# Pinduino-Nano-WPC-TPL521-v0_3c.net
KiCad netlist of a schematic drawn in EAGLE
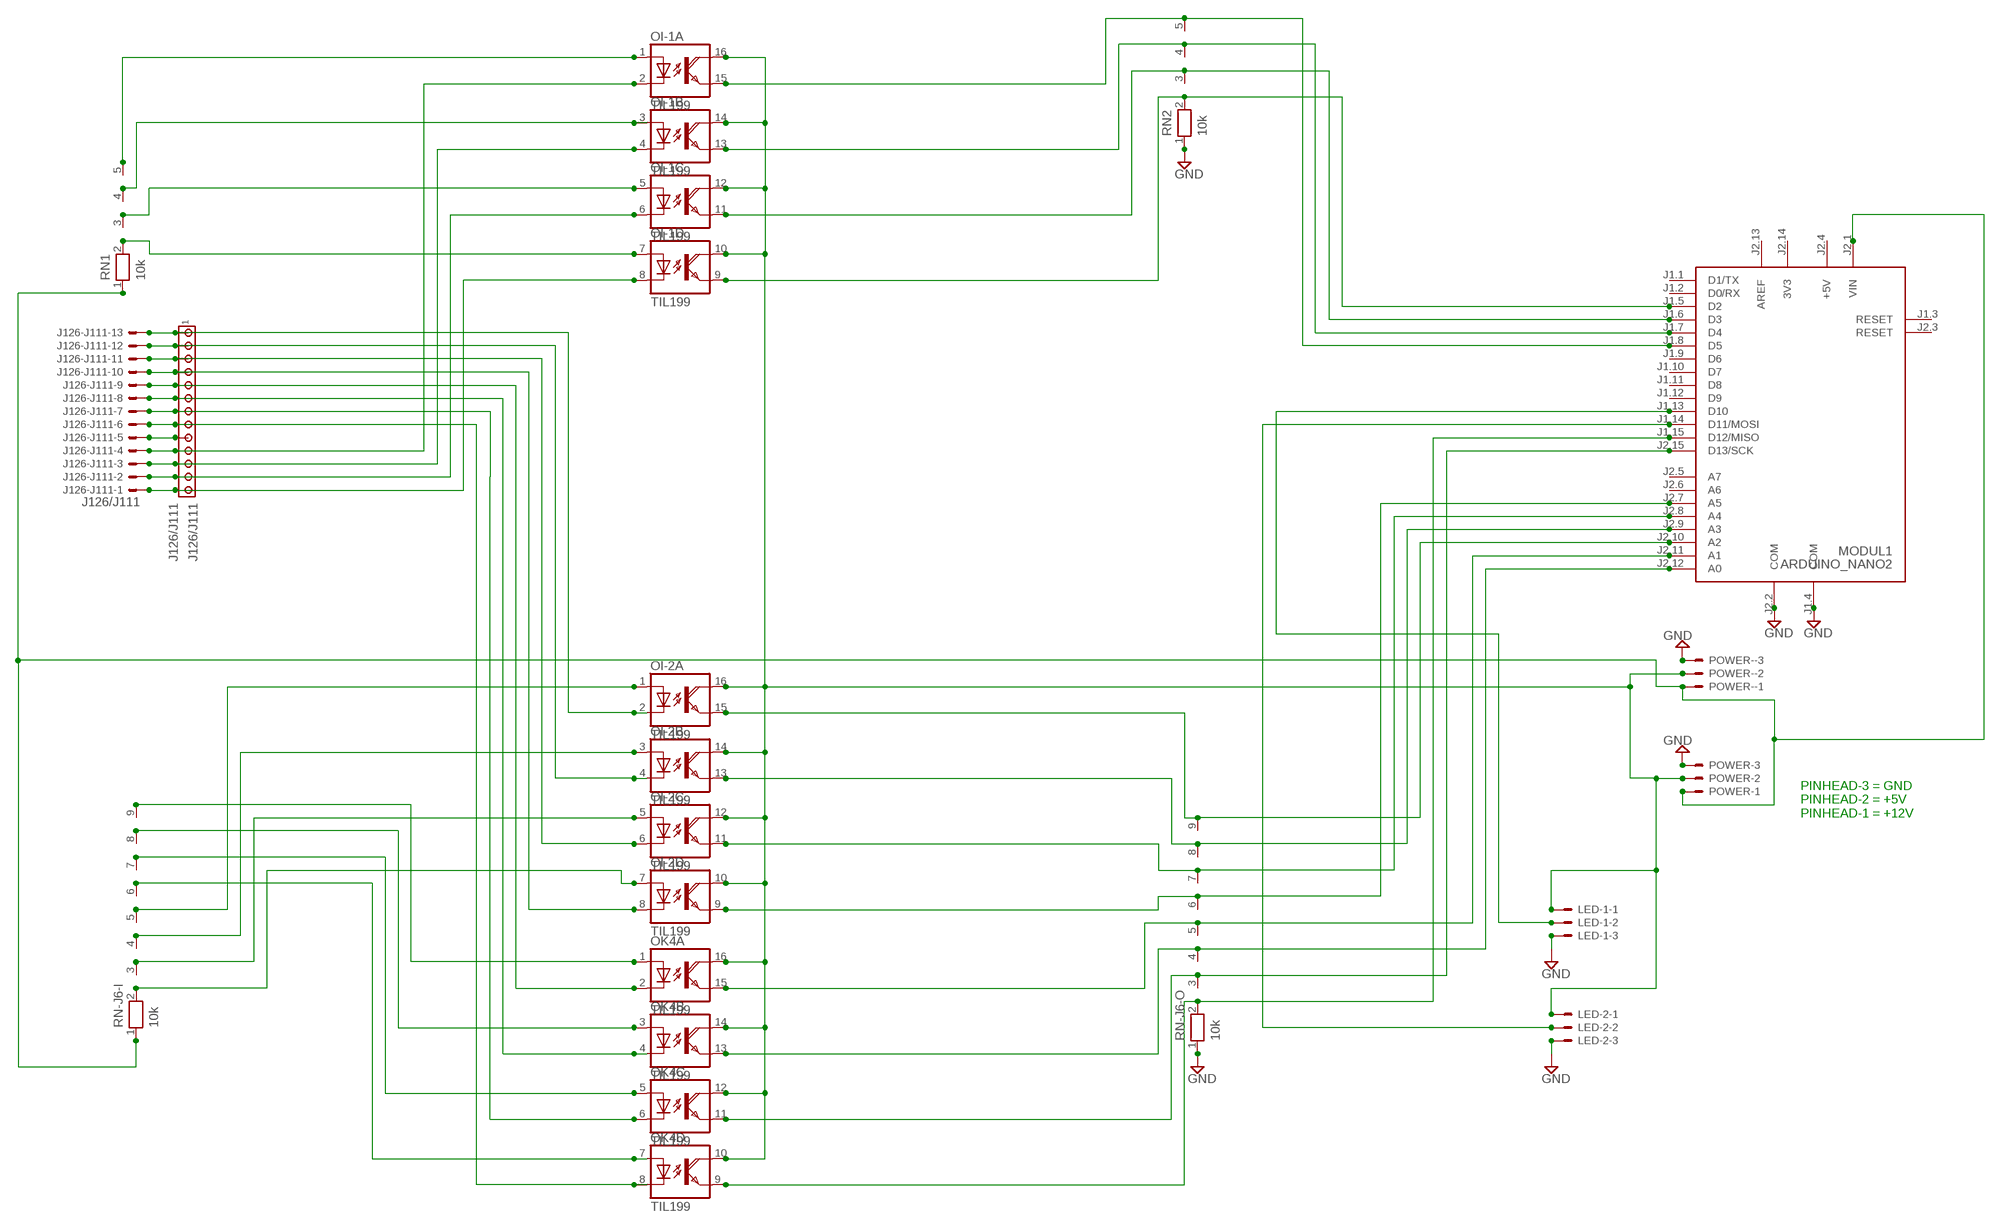
[diagram p0: schematic, sheet 1]

(export (version "E")
  (design (tool "Eeschema 10.0.6"))
  (components
    (comp (ref "J126-J111")
      (value "J126/J111")
      (footprint "eagle-import:KK-156-13")
      (libsource (lib "eagle-import") (part "KK-156-13"))
    )
    (comp (ref "J126/J111")
      (value "J126/J111")
      (footprint "eagle-import:1X13MTA")
      (libsource (lib "eagle-import") (part "MTA13-156"))
    )
    (comp (ref "LED-1")
      (value "22-23-2031")
      (footprint "eagle-import:22-23-2031")
      (fields (field (name "MF") "MOLEX"))
      (libsource (lib "eagle-import") (part "22-23-2031"))
    )
    (comp (ref "LED-2")
      (value "22-23-2031")
      (footprint "eagle-import:22-23-2031")
      (fields (field (name "MF") "MOLEX"))
      (libsource (lib "eagle-import") (part "22-23-2031"))
    )
    (comp (ref "MODUL1")
      (value "ARDUINO_NANO2")
      (footprint "eagle-import:ARDUINO_NANO2")
      (libsource (lib "eagle-import") (part "ARDUINO_NANO2"))
    )
    (comp (ref "OI-1")
      (value "TIL199")
      (footprint "eagle-import:DIL16")
      (fields (field (name "MPN") "TIL 199"))
      (libsource (lib "eagle-import") (part "TIL199"))
    )
    (comp (ref "OI-2")
      (value "TIL199")
      (footprint "eagle-import:DIL16")
      (fields (field (name "MPN") "TIL 199"))
      (libsource (lib "eagle-import") (part "TIL199"))
    )
    (comp (ref "OK4")
      (value "TIL199")
      (footprint "eagle-import:DIL16")
      (fields (field (name "MPN") "TIL 199"))
      (libsource (lib "eagle-import") (part "TIL199"))
    )
    (comp (ref "POWER")
      (value "22-23-2031")
      (footprint "eagle-import:22-23-2031")
      (fields (field (name "MF") "MOLEX"))
      (libsource (lib "eagle-import") (part "22-23-2031"))
    )
    (comp (ref "POWER-")
      (value "22-23-2031")
      (footprint "eagle-import:22-23-2031")
      (fields (field (name "MF") "MOLEX"))
      (libsource (lib "eagle-import") (part "22-23-2031"))
    )
    (comp (ref "RN-J6-I")
      (value "10k")
      (footprint "eagle-import:RN-9")
      (libsource (lib "eagle-import") (part "RN08"))
    )
    (comp (ref "RN-J6-O")
      (value "10k")
      (footprint "eagle-import:RN-9")
      (libsource (lib "eagle-import") (part "RN08"))
    )
    (comp (ref "RN1")
      (value "10k")
      (footprint "eagle-import:RN-5")
      (libsource (lib "eagle-import") (part "RN04"))
    )
    (comp (ref "RN2")
      (value "10k")
      (footprint "eagle-import:RN-5")
      (libsource (lib "eagle-import") (part "RN04"))
    )
  )
  (nets
    (net (code "1") (name "/+5V") (class "Default")
      (node (ref "MODUL1") (pin "J2.4") (pinfunction "+5V_J2.4") (pintype "power_in"))
    )
    (net (code "2") (name "/3V3") (class "Default")
      (node (ref "MODUL1") (pin "J2.14") (pinfunction "3V3_J2.14") (pintype "power_in"))
    )
    (net (code "3") (name "/AREF") (class "Default")
      (node (ref "MODUL1") (pin "J2.13") (pinfunction "AREF_J2.13") (pintype "power_in"))
    )
    (net (code "4") (name "GND") (class "Default")
      (node (ref "LED-1") (pin "3") (pinfunction "S_3") (pintype "passive"))
      (node (ref "LED-2") (pin "3") (pinfunction "S_3") (pintype "passive"))
      (node (ref "MODUL1") (pin "J1.4") (pinfunction "COM_J1.4") (pintype "power_in"))
      (node (ref "MODUL1") (pin "J2.2") (pinfunction "COM_J2.2") (pintype "power_in"))
      (node (ref "POWER") (pin "3") (pinfunction "S_3") (pintype "passive"))
      (node (ref "POWER-") (pin "3") (pinfunction "S_3") (pintype "passive"))
      (node (ref "RN-J6-O") (pin "1") (pinfunction "1_1") (pintype "passive"))
      (node (ref "RN2") (pin "1") (pinfunction "1_1") (pintype "passive"))
    )
    (net (code "5") (name "Net-(J126-J111A-S)") (class "Default")
      (node (ref "J126-J111") (pin "1") (pinfunction "S_1") (pintype "passive"))
      (node (ref "J126/J111") (pin "13") (pinfunction "13_13") (pintype "passive"))
      (node (ref "OI-1") (pin "8") (pinfunction "C_8") (pintype "passive"))
    )
    (net (code "6") (name "Net-(J126-J111B-S)") (class "Default")
      (node (ref "J126-J111") (pin "10") (pinfunction "S_10") (pintype "passive"))
      (node (ref "J126/J111") (pin "4") (pinfunction "4_4") (pintype "passive"))
      (node (ref "OI-2") (pin "8") (pinfunction "C_8") (pintype "passive"))
    )
    (net (code "7") (name "Net-(J126-J111C-S)") (class "Default")
      (node (ref "J126-J111") (pin "11") (pinfunction "S_11") (pintype "passive"))
      (node (ref "J126/J111") (pin "3") (pinfunction "3_3") (pintype "passive"))
      (node (ref "OI-2") (pin "6") (pinfunction "C_6") (pintype "passive"))
    )
    (net (code "8") (name "Net-(J126-J111D-S)") (class "Default")
      (node (ref "J126-J111") (pin "12") (pinfunction "S_12") (pintype "passive"))
      (node (ref "J126/J111") (pin "2") (pinfunction "2_2") (pintype "passive"))
      (node (ref "OI-2") (pin "4") (pinfunction "C_4") (pintype "passive"))
    )
    (net (code "9") (name "Net-(J126-J111E-S)") (class "Default")
      (node (ref "J126-J111") (pin "13") (pinfunction "S_13") (pintype "passive"))
      (node (ref "J126/J111") (pin "1") (pinfunction "1_1") (pintype "passive"))
      (node (ref "OI-2") (pin "2") (pinfunction "C_2") (pintype "passive"))
    )
    (net (code "10") (name "Net-(J126-J111F-S)") (class "Default")
      (node (ref "J126-J111") (pin "2") (pinfunction "S_2") (pintype "passive"))
      (node (ref "J126/J111") (pin "12") (pinfunction "12_12") (pintype "passive"))
      (node (ref "OI-1") (pin "6") (pinfunction "C_6") (pintype "passive"))
    )
    (net (code "11") (name "Net-(J126-J111G-S)") (class "Default")
      (node (ref "J126-J111") (pin "3") (pinfunction "S_3") (pintype "passive"))
      (node (ref "J126/J111") (pin "11") (pinfunction "11_11") (pintype "passive"))
      (node (ref "OI-1") (pin "4") (pinfunction "C_4") (pintype "passive"))
    )
    (net (code "12") (name "Net-(J126-J111H-S)") (class "Default")
      (node (ref "J126-J111") (pin "4") (pinfunction "S_4") (pintype "passive"))
      (node (ref "J126/J111") (pin "10") (pinfunction "10_10") (pintype "passive"))
      (node (ref "OI-1") (pin "2") (pinfunction "C_2") (pintype "passive"))
    )
    (net (code "13") (name "Net-(J126-J111I-S)") (class "Default")
      (node (ref "J126-J111") (pin "5") (pinfunction "S_5") (pintype "passive"))
      (node (ref "J126/J111") (pin "9") (pinfunction "9_9") (pintype "passive"))
    )
    (net (code "14") (name "Net-(J126-J111J-S)") (class "Default")
      (node (ref "J126-J111") (pin "6") (pinfunction "S_6") (pintype "passive"))
      (node (ref "J126/J111") (pin "8") (pinfunction "8_8") (pintype "passive"))
      (node (ref "OK4") (pin "8") (pinfunction "C_8") (pintype "passive"))
    )
    (net (code "15") (name "Net-(J126-J111K-S)") (class "Default")
      (node (ref "J126-J111") (pin "7") (pinfunction "S_7") (pintype "passive"))
      (node (ref "J126/J111") (pin "7") (pinfunction "7_7") (pintype "passive"))
      (node (ref "OK4") (pin "6") (pinfunction "C_6") (pintype "passive"))
    )
    (net (code "16") (name "Net-(J126-J111L-S)") (class "Default")
      (node (ref "J126-J111") (pin "8") (pinfunction "S_8") (pintype "passive"))
      (node (ref "J126/J111") (pin "6") (pinfunction "6_6") (pintype "passive"))
      (node (ref "OK4") (pin "4") (pinfunction "C_4") (pintype "passive"))
    )
    (net (code "17") (name "Net-(J126-J111M-S)") (class "Default")
      (node (ref "J126-J111") (pin "9") (pinfunction "S_9") (pintype "passive"))
      (node (ref "J126/J111") (pin "5") (pinfunction "5_5") (pintype "passive"))
      (node (ref "OK4") (pin "2") (pinfunction "C_2") (pintype "passive"))
    )
    (net (code "18") (name "Net-(LED-1A-S)") (class "Default")
      (node (ref "LED-1") (pin "1") (pinfunction "S_1") (pintype "passive"))
      (node (ref "LED-2") (pin "1") (pinfunction "S_1") (pintype "passive"))
      (node (ref "OI-1") (pin "10") (pinfunction "COL_10") (pintype "passive"))
      (node (ref "OI-1") (pin "12") (pinfunction "COL_12") (pintype "passive"))
      (node (ref "OI-1") (pin "14") (pinfunction "COL_14") (pintype "passive"))
      (node (ref "OI-1") (pin "16") (pinfunction "COL_16") (pintype "passive"))
      (node (ref "OI-2") (pin "10") (pinfunction "COL_10") (pintype "passive"))
      (node (ref "OI-2") (pin "12") (pinfunction "COL_12") (pintype "passive"))
      (node (ref "OI-2") (pin "14") (pinfunction "COL_14") (pintype "passive"))
      (node (ref "OI-2") (pin "16") (pinfunction "COL_16") (pintype "passive"))
      (node (ref "OK4") (pin "10") (pinfunction "COL_10") (pintype "passive"))
      (node (ref "OK4") (pin "12") (pinfunction "COL_12") (pintype "passive"))
      (node (ref "OK4") (pin "14") (pinfunction "COL_14") (pintype "passive"))
      (node (ref "OK4") (pin "16") (pinfunction "COL_16") (pintype "passive"))
      (node (ref "POWER") (pin "2") (pinfunction "S_2") (pintype "passive"))
      (node (ref "POWER-") (pin "2") (pinfunction "S_2") (pintype "passive"))
    )
    (net (code "19") (name "Net-(LED-1B-S)") (class "Default")
      (node (ref "LED-1") (pin "2") (pinfunction "S_2") (pintype "passive"))
      (node (ref "MODUL1") (pin "J1.13") (pinfunction "D10_J1.13") (pintype "bidirectional"))
    )
    (net (code "20") (name "Net-(LED-2B-S)") (class "Default")
      (node (ref "LED-2") (pin "2") (pinfunction "S_2") (pintype "passive"))
      (node (ref "MODUL1") (pin "J1.14") (pinfunction "D11/MOSI_J1.14") (pintype "bidirectional"))
    )
    (net (code "21") (name "Net-(MODUL1-A0)") (class "Default")
      (node (ref "MODUL1") (pin "J2.12") (pinfunction "A0_J2.12") (pintype "bidirectional"))
      (node (ref "OK4") (pin "13") (pinfunction "EMI_13") (pintype "passive"))
      (node (ref "RN-J6-O") (pin "4") (pinfunction "4_4") (pintype "passive"))
    )
    (net (code "22") (name "Net-(MODUL1-A1)") (class "Default")
      (node (ref "MODUL1") (pin "J2.11") (pinfunction "A1_J2.11") (pintype "bidirectional"))
      (node (ref "OK4") (pin "15") (pinfunction "EMI_15") (pintype "passive"))
      (node (ref "RN-J6-O") (pin "5") (pinfunction "5_5") (pintype "passive"))
    )
    (net (code "23") (name "Net-(MODUL1-A2)") (class "Default")
      (node (ref "MODUL1") (pin "J2.10") (pinfunction "A2_J2.10") (pintype "bidirectional"))
      (node (ref "OI-2") (pin "15") (pinfunction "EMI_15") (pintype "passive"))
      (node (ref "RN-J6-O") (pin "9") (pinfunction "9_9") (pintype "passive"))
    )
    (net (code "24") (name "Net-(MODUL1-A3)") (class "Default")
      (node (ref "MODUL1") (pin "J2.9") (pinfunction "A3_J2.9") (pintype "bidirectional"))
      (node (ref "OI-2") (pin "13") (pinfunction "EMI_13") (pintype "passive"))
      (node (ref "RN-J6-O") (pin "8") (pinfunction "8_8") (pintype "passive"))
    )
    (net (code "25") (name "Net-(MODUL1-A4)") (class "Default")
      (node (ref "MODUL1") (pin "J2.8") (pinfunction "A4_J2.8") (pintype "bidirectional"))
      (node (ref "OI-2") (pin "11") (pinfunction "EMI_11") (pintype "passive"))
      (node (ref "RN-J6-O") (pin "7") (pinfunction "7_7") (pintype "passive"))
    )
    (net (code "26") (name "Net-(MODUL1-A5)") (class "Default")
      (node (ref "MODUL1") (pin "J2.7") (pinfunction "A5_J2.7") (pintype "bidirectional"))
      (node (ref "OI-2") (pin "9") (pinfunction "EMI_9") (pintype "passive"))
      (node (ref "RN-J6-O") (pin "6") (pinfunction "6_6") (pintype "passive"))
    )
    (net (code "27") (name "Net-(MODUL1-D2)") (class "Default")
      (node (ref "MODUL1") (pin "J1.5") (pinfunction "D2_J1.5") (pintype "bidirectional"))
      (node (ref "OI-1") (pin "9") (pinfunction "EMI_9") (pintype "passive"))
      (node (ref "RN2") (pin "2") (pinfunction "2_2") (pintype "passive"))
    )
    (net (code "28") (name "Net-(MODUL1-D3)") (class "Default")
      (node (ref "MODUL1") (pin "J1.6") (pinfunction "D3_J1.6") (pintype "bidirectional"))
      (node (ref "OI-1") (pin "11") (pinfunction "EMI_11") (pintype "passive"))
      (node (ref "RN2") (pin "3") (pinfunction "3_3") (pintype "passive"))
    )
    (net (code "29") (name "Net-(MODUL1-D4)") (class "Default")
      (node (ref "MODUL1") (pin "J1.7") (pinfunction "D4_J1.7") (pintype "bidirectional"))
      (node (ref "OI-1") (pin "13") (pinfunction "EMI_13") (pintype "passive"))
      (node (ref "RN2") (pin "4") (pinfunction "4_4") (pintype "passive"))
    )
    (net (code "30") (name "Net-(MODUL1-D5)") (class "Default")
      (node (ref "MODUL1") (pin "J1.8") (pinfunction "D5_J1.8") (pintype "bidirectional"))
      (node (ref "OI-1") (pin "15") (pinfunction "EMI_15") (pintype "passive"))
      (node (ref "RN2") (pin "5") (pinfunction "5_5") (pintype "passive"))
    )
    (net (code "31") (name "Net-(MODUL1-D12{slash}MISO)") (class "Default")
      (node (ref "MODUL1") (pin "J1.15") (pinfunction "D12/MISO_J1.15") (pintype "bidirectional"))
      (node (ref "OK4") (pin "9") (pinfunction "EMI_9") (pintype "passive"))
      (node (ref "RN-J6-O") (pin "2") (pinfunction "2_2") (pintype "passive"))
    )
    (net (code "32") (name "Net-(MODUL1-D13{slash}SCK)") (class "Default")
      (node (ref "MODUL1") (pin "J2.15") (pinfunction "D13/SCK_J2.15") (pintype "bidirectional"))
      (node (ref "OK4") (pin "11") (pinfunction "EMI_11") (pintype "passive"))
      (node (ref "RN-J6-O") (pin "3") (pinfunction "3_3") (pintype "passive"))
    )
    (net (code "33") (name "Net-(MODUL1-VIN)") (class "Default")
      (node (ref "MODUL1") (pin "J2.1") (pinfunction "VIN_J2.1") (pintype "power_in"))
      (node (ref "POWER") (pin "1") (pinfunction "S_1") (pintype "passive"))
      (node (ref "POWER-") (pin "1") (pinfunction "S_1") (pintype "passive"))
      (node (ref "RN-J6-I") (pin "1") (pinfunction "1_1") (pintype "passive"))
      (node (ref "RN1") (pin "1") (pinfunction "1_1") (pintype "passive"))
    )
    (net (code "34") (name "Net-(OI-1A-A)") (class "Default")
      (node (ref "OI-1") (pin "1") (pinfunction "A_1") (pintype "passive"))
      (node (ref "RN1") (pin "5") (pinfunction "5_5") (pintype "passive"))
    )
    (net (code "35") (name "Net-(OI-1B-A)") (class "Default")
      (node (ref "OI-1") (pin "3") (pinfunction "A_3") (pintype "passive"))
      (node (ref "RN1") (pin "4") (pinfunction "4_4") (pintype "passive"))
    )
    (net (code "36") (name "Net-(OI-1C-A)") (class "Default")
      (node (ref "OI-1") (pin "5") (pinfunction "A_5") (pintype "passive"))
      (node (ref "RN1") (pin "3") (pinfunction "3_3") (pintype "passive"))
    )
    (net (code "37") (name "Net-(OI-1D-A)") (class "Default")
      (node (ref "OI-1") (pin "7") (pinfunction "A_7") (pintype "passive"))
      (node (ref "RN1") (pin "2") (pinfunction "2_2") (pintype "passive"))
    )
    (net (code "38") (name "Net-(OI-2A-A)") (class "Default")
      (node (ref "OI-2") (pin "1") (pinfunction "A_1") (pintype "passive"))
      (node (ref "RN-J6-I") (pin "5") (pinfunction "5_5") (pintype "passive"))
    )
    (net (code "39") (name "Net-(OI-2B-A)") (class "Default")
      (node (ref "OI-2") (pin "3") (pinfunction "A_3") (pintype "passive"))
      (node (ref "RN-J6-I") (pin "4") (pinfunction "4_4") (pintype "passive"))
    )
    (net (code "40") (name "Net-(OI-2C-A)") (class "Default")
      (node (ref "OI-2") (pin "5") (pinfunction "A_5") (pintype "passive"))
      (node (ref "RN-J6-I") (pin "3") (pinfunction "3_3") (pintype "passive"))
    )
    (net (code "41") (name "Net-(OI-2D-A)") (class "Default")
      (node (ref "OI-2") (pin "7") (pinfunction "A_7") (pintype "passive"))
      (node (ref "RN-J6-I") (pin "2") (pinfunction "2_2") (pintype "passive"))
    )
    (net (code "42") (name "Net-(OK4A-A)") (class "Default")
      (node (ref "OK4") (pin "1") (pinfunction "A_1") (pintype "passive"))
      (node (ref "RN-J6-I") (pin "9") (pinfunction "9_9") (pintype "passive"))
    )
    (net (code "43") (name "Net-(OK4B-A)") (class "Default")
      (node (ref "OK4") (pin "3") (pinfunction "A_3") (pintype "passive"))
      (node (ref "RN-J6-I") (pin "8") (pinfunction "8_8") (pintype "passive"))
    )
    (net (code "44") (name "Net-(OK4C-A)") (class "Default")
      (node (ref "OK4") (pin "5") (pinfunction "A_5") (pintype "passive"))
      (node (ref "RN-J6-I") (pin "7") (pinfunction "7_7") (pintype "passive"))
    )
    (net (code "45") (name "Net-(OK4D-A)") (class "Default")
      (node (ref "OK4") (pin "7") (pinfunction "A_7") (pintype "passive"))
      (node (ref "RN-J6-I") (pin "6") (pinfunction "6_6") (pintype "passive"))
    )
    (net (code "46") (name "unconnected-(MODUL1-A6-PadJ2.6)") (class "Default")
      (node (ref "MODUL1") (pin "J2.6") (pinfunction "A6_J2.6") (pintype "bidirectional"))
    )
    (net (code "47") (name "unconnected-(MODUL1-A7-PadJ2.5)") (class "Default")
      (node (ref "MODUL1") (pin "J2.5") (pinfunction "A7_J2.5") (pintype "bidirectional"))
    )
    (net (code "48") (name "unconnected-(MODUL1-D0{slash}RX-PadJ1.2)") (class "Default")
      (node (ref "MODUL1") (pin "J1.2") (pinfunction "D0/RX_J1.2") (pintype "bidirectional"))
    )
    (net (code "49") (name "unconnected-(MODUL1-D1{slash}TX-PadJ1.1)") (class "Default")
      (node (ref "MODUL1") (pin "J1.1") (pinfunction "D1/TX_J1.1") (pintype "bidirectional"))
    )
    (net (code "50") (name "unconnected-(MODUL1-D6-PadJ1.9)") (class "Default")
      (node (ref "MODUL1") (pin "J1.9") (pinfunction "D6_J1.9") (pintype "bidirectional"))
    )
    (net (code "51") (name "unconnected-(MODUL1-D7-PadJ1.10)") (class "Default")
      (node (ref "MODUL1") (pin "J1.10") (pinfunction "D7_J1.10") (pintype "bidirectional"))
    )
    (net (code "52") (name "unconnected-(MODUL1-D8-PadJ1.11)") (class "Default")
      (node (ref "MODUL1") (pin "J1.11") (pinfunction "D8_J1.11") (pintype "bidirectional"))
    )
    (net (code "53") (name "unconnected-(MODUL1-D9-PadJ1.12)") (class "Default")
      (node (ref "MODUL1") (pin "J1.12") (pinfunction "D9_J1.12") (pintype "bidirectional"))
    )
    (net (code "54") (name "unconnected-(MODUL1-RESET-PadJ1.3)") (class "Default")
      (node (ref "MODUL1") (pin "J1.3") (pinfunction "RESET_J1.3") (pintype "bidirectional"))
    )
    (net (code "55") (name "unconnected-(MODUL1-RESET-PadJ2.3)") (class "Default")
      (node (ref "MODUL1") (pin "J2.3") (pinfunction "RESET_J2.3") (pintype "bidirectional"))
    )
  )
)
